# ghetto_distortion_Vold.net
KiCad netlist of a schematic drawn in EAGLE
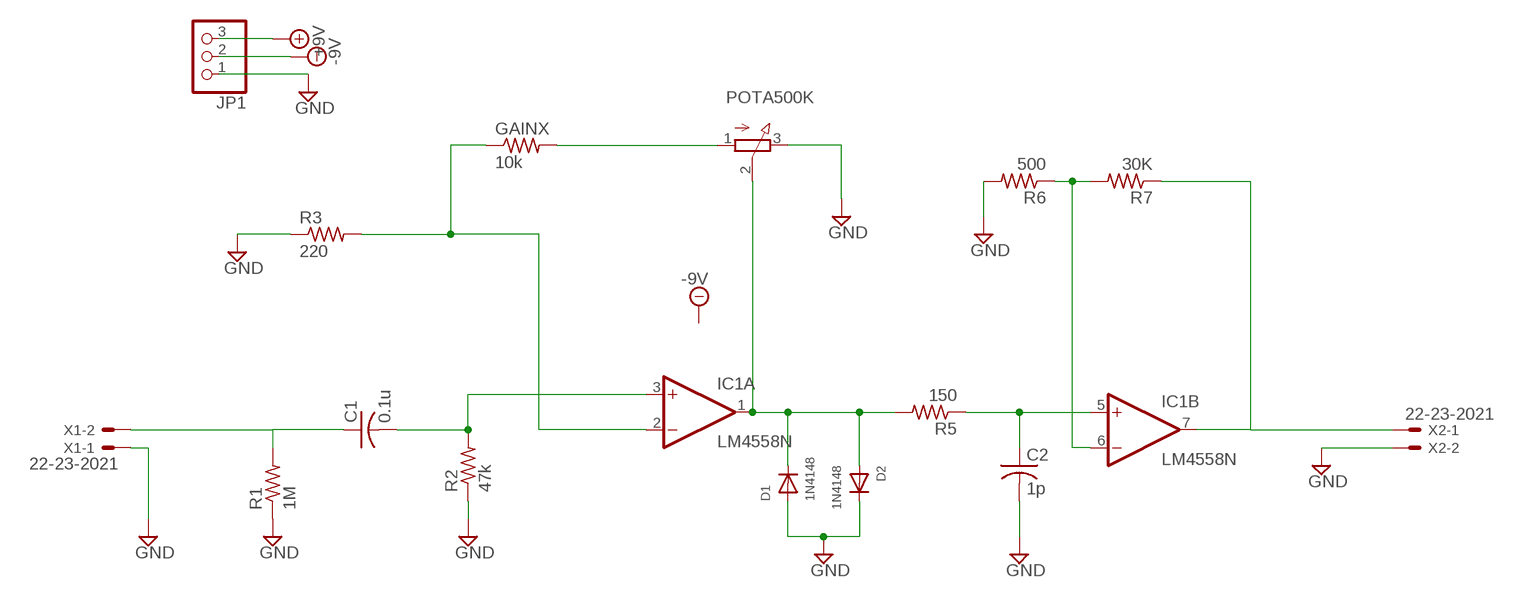
[diagram p0: schematic, sheet 1]

(export (version "E")
  (design (tool "Eeschema 10.0.6"))
  (components
    (comp (ref "C1")
      (value "0.1u")
      (footprint "eagle-import:C050-024X044")
      (libsource (lib "eagle-import") (part "C-US050-024X044"))
    )
    (comp (ref "C2")
      (value "1p")
      (footprint "eagle-import:C050-024X044")
      (libsource (lib "eagle-import") (part "C-US050-024X044"))
    )
    (comp (ref "D1")
      (value "1N4148")
      (footprint "eagle-import:DO-1N4148")
      (libsource (lib "eagle-import") (part "DIODEDO-1N4148"))
    )
    (comp (ref "D2")
      (value "1N4148")
      (footprint "eagle-import:DO-1N4148")
      (libsource (lib "eagle-import") (part "DIODEDO-1N4148"))
    )
    (comp (ref "GAINX")
      (value "10k")
      (footprint "eagle-import:0204_7")
      (libsource (lib "eagle-import") (part "R-US_0204/7"))
    )
    (comp (ref "IC1")
      (value "LM4558N")
      (footprint "eagle-import:DIL08")
      (libsource (lib "eagle-import") (part "4558NLM"))
    )
    (comp (ref "JP1")
      (value "PINHD-1X3")
      (footprint "eagle-import:1X03")
      (libsource (lib "eagle-import") (part "PINHD-1X3"))
    )
    (comp (ref "POTA500K")
      (value "3RP/1610N")
      (footprint "eagle-import:3RP_1610N")
      (libsource (lib "eagle-import") (part "3RP/1610N"))
    )
    (comp (ref "R1")
      (value "1M")
      (footprint "eagle-import:0204_7")
      (libsource (lib "eagle-import") (part "R-US_0204/7"))
    )
    (comp (ref "R2")
      (value "47k")
      (footprint "eagle-import:0204_7")
      (libsource (lib "eagle-import") (part "R-US_0204/7"))
    )
    (comp (ref "R3")
      (value "220")
      (footprint "eagle-import:0204_7")
      (libsource (lib "eagle-import") (part "R-US_0204/7"))
    )
    (comp (ref "R5")
      (value "150")
      (footprint "eagle-import:0204_7")
      (libsource (lib "eagle-import") (part "R-US_0204/7"))
    )
    (comp (ref "R6")
      (value "500")
      (footprint "eagle-import:0204_7")
      (libsource (lib "eagle-import") (part "R-US_0204/7"))
    )
    (comp (ref "R7")
      (value "30K")
      (footprint "eagle-import:0204_7")
      (libsource (lib "eagle-import") (part "R-US_0204/7"))
    )
    (comp (ref "X1")
      (value "22-23-2021")
      (footprint "eagle-import:22-23-2021")
      (fields (field (name "MF") "MOLEX"))
      (libsource (lib "eagle-import") (part "22-23-2021"))
    )
    (comp (ref "X2")
      (value "22-23-2021")
      (footprint "eagle-import:22-23-2021")
      (fields (field (name "MF") "MOLEX"))
      (libsource (lib "eagle-import") (part "22-23-2021"))
    )
  )
  (nets
    (net (code "1") (name "+9V") (class "Default")
      (node (ref "JP1") (pin "3") (pinfunction "3_3") (pintype "passive"))
    )
    (net (code "2") (name "-9V") (class "Default")
      (node (ref "JP1") (pin "2") (pinfunction "2_2") (pintype "passive"))
    )
    (net (code "3") (name "GND") (class "Default")
      (node (ref "C2") (pin "2") (pinfunction "2_2") (pintype "passive"))
      (node (ref "D1") (pin "A") (pinfunction "A_A") (pintype "passive"))
      (node (ref "D2") (pin "C") (pinfunction "C_C") (pintype "passive"))
      (node (ref "JP1") (pin "1") (pinfunction "1_1") (pintype "passive"))
      (node (ref "POTA500K") (pin "3") (pinfunction "E_3") (pintype "passive"))
      (node (ref "R1") (pin "1") (pinfunction "1_1") (pintype "passive"))
      (node (ref "R2") (pin "1") (pinfunction "1_1") (pintype "passive"))
      (node (ref "R3") (pin "1") (pinfunction "1_1") (pintype "passive"))
      (node (ref "R6") (pin "2") (pinfunction "2_2") (pintype "passive"))
      (node (ref "X1") (pin "1") (pinfunction "S_1") (pintype "passive"))
      (node (ref "X2") (pin "2") (pinfunction "S_2") (pintype "passive"))
    )
    (net (code "4") (name "Net-(IC1A-+IN)") (class "Default")
      (node (ref "C1") (pin "2") (pinfunction "2_2") (pintype "passive"))
      (node (ref "IC1") (pin "3") (pinfunction "+IN_3") (pintype "input"))
      (node (ref "R2") (pin "2") (pinfunction "2_2") (pintype "passive"))
    )
    (net (code "5") (name "Net-(IC1A--IN)") (class "Default")
      (node (ref "GAINX") (pin "1") (pinfunction "1_1") (pintype "passive"))
      (node (ref "IC1") (pin "2") (pinfunction "-IN_2") (pintype "input"))
      (node (ref "R3") (pin "2") (pinfunction "2_2") (pintype "passive"))
    )
    (net (code "6") (name "Net-(IC1A-OUT)") (class "Default")
      (node (ref "D1") (pin "C") (pinfunction "C_C") (pintype "passive"))
      (node (ref "D2") (pin "A") (pinfunction "A_A") (pintype "passive"))
      (node (ref "IC1") (pin "1") (pinfunction "OUT_1") (pintype "output"))
      (node (ref "POTA500K") (pin "2") (pinfunction "S_2") (pintype "passive"))
      (node (ref "R5") (pin "2") (pinfunction "2_2") (pintype "passive"))
    )
    (net (code "7") (name "Net-(IC1B-+IN)") (class "Default")
      (node (ref "C2") (pin "1") (pinfunction "1_1") (pintype "passive"))
      (node (ref "IC1") (pin "5") (pinfunction "+IN_5") (pintype "input"))
      (node (ref "R5") (pin "1") (pinfunction "1_1") (pintype "passive"))
    )
    (net (code "8") (name "Net-(IC1B--IN)") (class "Default")
      (node (ref "IC1") (pin "6") (pinfunction "-IN_6") (pintype "input"))
      (node (ref "R6") (pin "1") (pinfunction "1_1") (pintype "passive"))
      (node (ref "R7") (pin "2") (pinfunction "2_2") (pintype "passive"))
    )
    (net (code "9") (name "Net-(IC1B-OUT)") (class "Default")
      (node (ref "IC1") (pin "7") (pinfunction "OUT_7") (pintype "output"))
      (node (ref "R7") (pin "1") (pinfunction "1_1") (pintype "passive"))
      (node (ref "X2") (pin "1") (pinfunction "S_1") (pintype "passive"))
    )
    (net (code "10") (name "Net-(POTA500K-A)") (class "Default")
      (node (ref "GAINX") (pin "2") (pinfunction "2_2") (pintype "passive"))
      (node (ref "POTA500K") (pin "1") (pinfunction "A_1") (pintype "passive"))
    )
    (net (code "11") (name "Net-(X1B-S)") (class "Default")
      (node (ref "C1") (pin "1") (pinfunction "1_1") (pintype "passive"))
      (node (ref "R1") (pin "2") (pinfunction "2_2") (pintype "passive"))
      (node (ref "X1") (pin "2") (pinfunction "S_2") (pintype "passive"))
    )
  )
)
